# Headers.net
KiCad netlist of a schematic drawn in Altium Designer
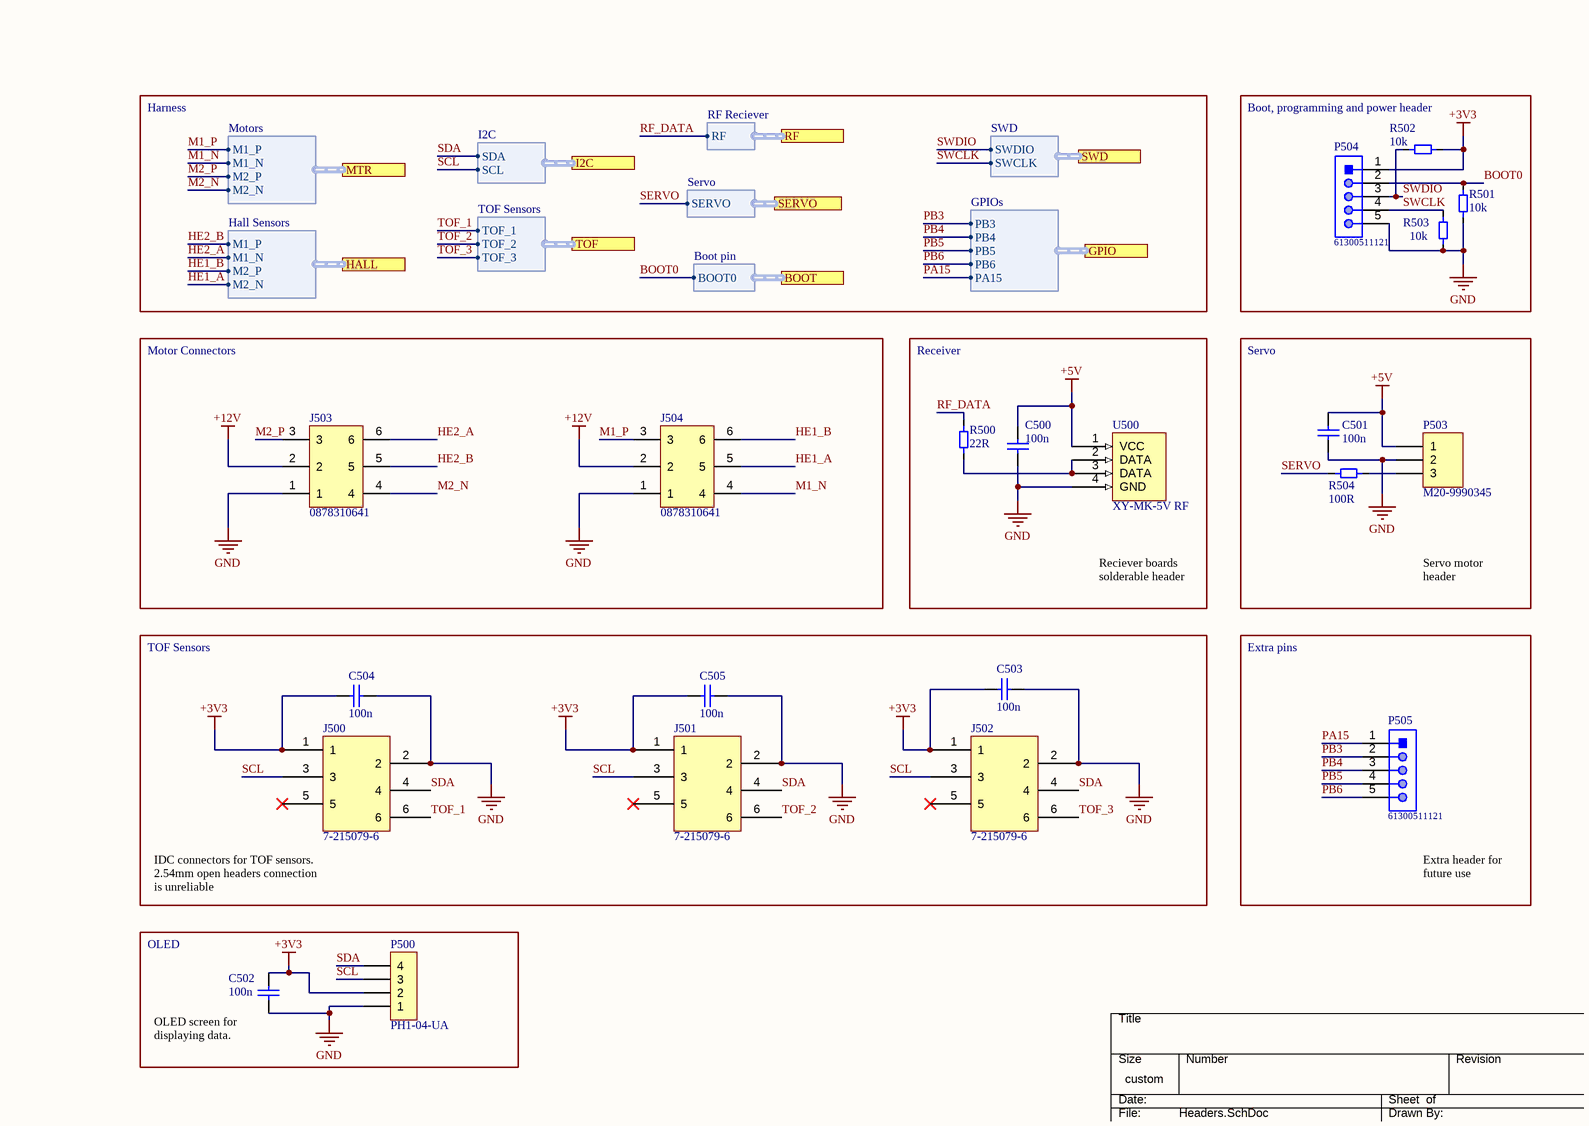
[diagram p0: Headers.SchDoc]

(export (version "E")
  (design (tool "Eeschema 10.0.6"))
  (components
    (comp (ref "C500")
      (value "100n")
      (footprint "MLCC_0603_M")
      (description "MLCC, 0603, 100n, 10%, 50V, X7R")
      (fields (field (name "VOLTAGE") "50V") (field (name "TOLERANCE") "10%"))
      (libsource (lib "Krakul Vault") (part "CAPACITOR_NONPOL_IEC"))
    )
    (comp (ref "C501")
      (value "100n")
      (footprint "MLCC_0603_M")
      (description "MLCC, 0603, 100n, 10%, 50V, X7R")
      (fields (field (name "VOLTAGE") "50V") (field (name "TOLERANCE") "10%"))
      (libsource (lib "Krakul Vault") (part "CAPACITOR_NONPOL_IEC"))
    )
    (comp (ref "C502")
      (value "100n")
      (footprint "MLCC_0603_M")
      (description "MLCC, 0603, 100n, 10%, 50V, X7R")
      (fields (field (name "VOLTAGE") "50V") (field (name "TOLERANCE") "10%"))
      (libsource (lib "Krakul Vault") (part "CAPACITOR_NONPOL_IEC"))
    )
    (comp (ref "C503")
      (value "100n")
      (footprint "MLCC_0603_M")
      (description "MLCC, 0603, 100n, 10%, 50V, X7R")
      (fields (field (name "VOLTAGE") "50V") (field (name "TOLERANCE") "10%"))
      (libsource (lib "Krakul Vault") (part "CAPACITOR_NONPOL_IEC"))
    )
    (comp (ref "C504")
      (value "100n")
      (footprint "MLCC_0603_M")
      (description "MLCC, 0603, 100n, 10%, 50V, X7R")
      (fields (field (name "VOLTAGE") "50V") (field (name "TOLERANCE") "10%"))
      (libsource (lib "Krakul Vault") (part "CAPACITOR_NONPOL_IEC"))
    )
    (comp (ref "C505")
      (value "100n")
      (footprint "MLCC_0603_M")
      (description "MLCC, 0603, 100n, 10%, 50V, X7R")
      (fields (field (name "VOLTAGE") "50V") (field (name "TOLERANCE") "10%"))
      (libsource (lib "Krakul Vault") (part "CAPACITOR_NONPOL_IEC"))
    )
    (comp (ref "J500")
      (value "7-215079-6")
      (footprint "7-215079-6-Footprint-1")
      (description "Conn FFC Connector F 6 POS 1.27mm Solder ST Thru-Hole Automotive Box/Carton")
      (fields (field (name "MANUFACTURER") "TE Connectivity"))
      (libsource (lib "Krakul Vault") (part "7-215079-6"))
    )
    (comp (ref "J501")
      (value "7-215079-6")
      (footprint "7-215079-6-Footprint-1")
      (description "Conn FFC Connector F 6 POS 1.27mm Solder ST Thru-Hole Automotive Box/Carton")
      (fields (field (name "MANUFACTURER") "TE Connectivity"))
      (libsource (lib "Krakul Vault") (part "7-215079-6"))
    )
    (comp (ref "J502")
      (value "7-215079-6")
      (footprint "7-215079-6-Footprint-1")
      (description "Conn FFC Connector F 6 POS 1.27mm Solder ST Thru-Hole Automotive Box/Carton")
      (fields (field (name "MANUFACTURER") "TE Connectivity"))
      (libsource (lib "Krakul Vault") (part "7-215079-6"))
    )
    (comp (ref "J503")
      (value "0878310641")
      (footprint "0878310641")
      (description "Conn Shrouded Header (2 Sides) HDR 6 POS 2mm Solder ST Top Entry Thru-Hole Milli-Grid Tube")
      (fields (field (name "MANUFACTURER") "Molex"))
      (libsource (lib "Krakul Vault") (part "0878310641"))
    )
    (comp (ref "J504")
      (value "0878310641")
      (footprint "0878310641")
      (description "Conn Shrouded Header (2 Sides) HDR 6 POS 2mm Solder ST Top Entry Thru-Hole Milli-Grid Tube")
      (fields (field (name "MANUFACTURER") "Molex"))
      (libsource (lib "Krakul Vault") (part "0878310641"))
    )
    (comp (ref "P500")
      (value "PH1-04-UA")
      (footprint "4Pos Pin Header Vertical")
      (description "4 POS 2.54mm Vertical THT Header")
      (fields (field (name "MANUFACTURER") "Adam Tech"))
      (libsource (lib "Krakul Vault") (part "4POS GENERIC"))
    )
    (comp (ref "P503")
      (value "M20-9990345")
      (footprint "3Pos Pin Header")
      (description "Connector Header Through Hole 3 position 0.100\" (2.54mm)")
      (fields (field (name "MANUFACTURER") "Harwin Inc."))
      (libsource (lib "Krakul Vault") (part "3 pin header"))
    )
    (comp (ref "P504")
      (value "61300511121")
      (footprint "61300511121")
      (description "Conn Unshrouded Header HDR 5 POS 2.54mm Solder ST Top Entry Thru-Hole Bag")
      (fields (field (name "MANUFACTURER") "Wurth"))
      (libsource (lib "") (part "WE-CN-1P-M-R5_1"))
    )
    (comp (ref "P505")
      (value "61300511121")
      (footprint "61300511121")
      (description "Conn Unshrouded Header HDR 5 POS 2.54mm Solder ST Top Entry Thru-Hole Bag")
      (fields (field (name "MANUFACTURER") "Wurth"))
      (libsource (lib "Krakul Vault") (part "WE-CN-1P-M-R5"))
    )
    (comp (ref "R500")
      (value "22R")
      (footprint "Resistor_0603_M")
      (description "Resistor, 0603, 22R, 1%, 1/10W")
      (fields (field (name "TOLERANCE") "1%") (field (name "MANUFACTURER") "Any"))
      (libsource (lib "Krakul Vault") (part "RESISTOR_GENERIC_IEC"))
    )
    (comp (ref "R501")
      (value "10k")
      (footprint "Resistor_0603_M")
      (description "Resistor, 0603, 10k, ≤5%, ≥1/16W")
      (fields (field (name "MANUFACTURER") "Any"))
      (libsource (lib "Krakul Vault") (part "RESISTOR_GENERIC_IEC"))
    )
    (comp (ref "R502")
      (value "10k")
      (footprint "Resistor_0603_M")
      (description "Resistor, 0603, 10k, 1%, 1/10W")
      (fields (field (name "MANUFACTURER") "Any") (field (name "TOLERANCE") "1%"))
      (libsource (lib "Krakul Vault") (part "RESISTOR_GENERIC_IEC"))
    )
    (comp (ref "R503")
      (value "10k")
      (footprint "Resistor_0603_M")
      (description "Resistor, 0603, 10k, 1%, 1/10W")
      (fields (field (name "MANUFACTURER") "Any") (field (name "TOLERANCE") "1%"))
      (libsource (lib "Krakul Vault") (part "RESISTOR_GENERIC_IEC"))
    )
    (comp (ref "R504")
      (value "100R")
      (footprint "Resistor_0603_M")
      (description "Resistor, 0603, 100R, 1%, 1/10W")
      (fields (field (name "POWER") "100mW") (field (name "MANUFACTURER") "Any"))
      (libsource (lib "Krakul Vault") (part "RESISTOR_GENERIC_IEC"))
    )
    (comp (ref "U500")
      (value "XY-MK-5V RF")
      (footprint "2.54mm 4 POS XY-MK-5V RF")
      (description "433MHz reciever module, 5V tolerant")
      (fields (field (name "MANUFACTURER") "Unknown"))
      (libsource (lib "Krakul Vault") (part "XY-MK-5V RF-Symbol-1"))
    )
  )
  (nets
    (net (code "13") (name "+3V3") (class "Default")
      (node (ref "C502") (pin "1") (pinfunction "1_1") (pintype "passive"))
      (node (ref "C503") (pin "1") (pinfunction "1_1") (pintype "passive"))
      (node (ref "C504") (pin "1") (pinfunction "1_1") (pintype "passive"))
      (node (ref "C505") (pin "1") (pinfunction "1_1") (pintype "passive"))
      (node (ref "J500") (pin "1") (pinfunction "1_1") (pintype "passive"))
      (node (ref "J501") (pin "1") (pinfunction "1_1") (pintype "passive"))
      (node (ref "J502") (pin "1") (pinfunction "1_1") (pintype "passive"))
      (node (ref "P500") (pin "2") (pinfunction "2_2") (pintype "passive"))
      (node (ref "P504") (pin "1") (pinfunction "1_1") (pintype "passive"))
      (node (ref "R502") (pin "1") (pinfunction "1_1") (pintype "passive"))
    )
    (net (code "14") (name "+5V") (class "Default")
      (node (ref "C500") (pin "1") (pinfunction "1_1") (pintype "passive"))
      (node (ref "C501") (pin "1") (pinfunction "1_1") (pintype "passive"))
      (node (ref "P503") (pin "1") (pinfunction "1_1") (pintype "passive"))
      (node (ref "U500") (pin "1") (pinfunction "VCC_1") (pintype "input"))
    )
    (net (code "15") (name "+12V") (class "Default")
      (node (ref "J503") (pin "2") (pinfunction "2_2") (pintype "passive"))
      (node (ref "J504") (pin "2") (pinfunction "2_2") (pintype "passive"))
    )
    (net (code "16") (name "/BOOT0") (class "Default")
      (node (ref "P504") (pin "2") (pinfunction "2_2") (pintype "passive"))
      (node (ref "R501") (pin "2") (pinfunction "2_2") (pintype "passive"))
    )
    (net (code "17") (name "/HE1_A") (class "Default")
      (node (ref "J504") (pin "5") (pinfunction "5_5") (pintype "passive"))
    )
    (net (code "18") (name "/HE1_B") (class "Default")
      (node (ref "J504") (pin "6") (pinfunction "6_6") (pintype "passive"))
    )
    (net (code "19") (name "/HE2_A") (class "Default")
      (node (ref "J503") (pin "6") (pinfunction "6_6") (pintype "passive"))
    )
    (net (code "20") (name "/HE2_B") (class "Default")
      (node (ref "J503") (pin "5") (pinfunction "5_5") (pintype "passive"))
    )
    (net (code "21") (name "/M1_N") (class "Default")
      (node (ref "J504") (pin "4") (pinfunction "4_4") (pintype "passive"))
    )
    (net (code "22") (name "/M1_P") (class "Default")
      (node (ref "J504") (pin "3") (pinfunction "3_3") (pintype "passive"))
    )
    (net (code "23") (name "/M2_N") (class "Default")
      (node (ref "J503") (pin "4") (pinfunction "4_4") (pintype "passive"))
    )
    (net (code "24") (name "/M2_P") (class "Default")
      (node (ref "J503") (pin "3") (pinfunction "3_3") (pintype "passive"))
    )
    (net (code "25") (name "/PA15") (class "Default")
      (node (ref "P505") (pin "1") (pinfunction "1_1") (pintype "passive"))
    )
    (net (code "26") (name "/PB3") (class "Default")
      (node (ref "P505") (pin "2") (pinfunction "2_2") (pintype "passive"))
    )
    (net (code "27") (name "/PB4") (class "Default")
      (node (ref "P505") (pin "3") (pinfunction "3_3") (pintype "passive"))
    )
    (net (code "28") (name "/PB5") (class "Default")
      (node (ref "P505") (pin "4") (pinfunction "4_4") (pintype "passive"))
    )
    (net (code "29") (name "/PB6") (class "Default")
      (node (ref "P505") (pin "5") (pinfunction "5_5") (pintype "passive"))
    )
    (net (code "30") (name "/RF_DATA") (class "Default")
      (node (ref "R500") (pin "1") (pinfunction "1_1") (pintype "passive"))
    )
    (net (code "31") (name "/SCL") (class "Default")
      (node (ref "J500") (pin "3") (pinfunction "3_3") (pintype "passive"))
      (node (ref "J501") (pin "3") (pinfunction "3_3") (pintype "passive"))
      (node (ref "J502") (pin "3") (pinfunction "3_3") (pintype "passive"))
      (node (ref "P500") (pin "3") (pinfunction "3_3") (pintype "passive"))
    )
    (net (code "32") (name "/SDA") (class "Default")
      (node (ref "J500") (pin "4") (pinfunction "4_4") (pintype "passive"))
      (node (ref "J501") (pin "4") (pinfunction "4_4") (pintype "passive"))
      (node (ref "J502") (pin "4") (pinfunction "4_4") (pintype "passive"))
      (node (ref "P500") (pin "4") (pinfunction "4_4") (pintype "passive"))
    )
    (net (code "33") (name "/SERVO") (class "Default")
      (node (ref "R504") (pin "2") (pinfunction "2_2") (pintype "passive"))
    )
    (net (code "34") (name "/SWCLK") (class "Default")
      (node (ref "P504") (pin "4") (pinfunction "4_4") (pintype "passive"))
      (node (ref "R503") (pin "2") (pinfunction "2_2") (pintype "passive"))
    )
    (net (code "35") (name "/SWDIO") (class "Default")
      (node (ref "P504") (pin "3") (pinfunction "3_3") (pintype "passive"))
      (node (ref "R502") (pin "2") (pinfunction "2_2") (pintype "passive"))
    )
    (net (code "36") (name "/TOF_1") (class "Default")
      (node (ref "J500") (pin "6") (pinfunction "6_6") (pintype "passive"))
    )
    (net (code "37") (name "/TOF_2") (class "Default")
      (node (ref "J501") (pin "6") (pinfunction "6_6") (pintype "passive"))
    )
    (net (code "38") (name "/TOF_3") (class "Default")
      (node (ref "J502") (pin "6") (pinfunction "6_6") (pintype "passive"))
    )
    (net (code "48") (name "GND") (class "Default")
      (node (ref "C500") (pin "2") (pinfunction "2_2") (pintype "passive"))
      (node (ref "C501") (pin "2") (pinfunction "2_2") (pintype "passive"))
      (node (ref "C502") (pin "2") (pinfunction "2_2") (pintype "passive"))
      (node (ref "C503") (pin "2") (pinfunction "2_2") (pintype "passive"))
      (node (ref "C504") (pin "2") (pinfunction "2_2") (pintype "passive"))
      (node (ref "C505") (pin "2") (pinfunction "2_2") (pintype "passive"))
      (node (ref "J500") (pin "2") (pinfunction "2_2") (pintype "passive"))
      (node (ref "J501") (pin "2") (pinfunction "2_2") (pintype "passive"))
      (node (ref "J502") (pin "2") (pinfunction "2_2") (pintype "passive"))
      (node (ref "J503") (pin "1") (pinfunction "1_1") (pintype "passive"))
      (node (ref "J504") (pin "1") (pinfunction "1_1") (pintype "passive"))
      (node (ref "P500") (pin "1") (pinfunction "1_1") (pintype "passive"))
      (node (ref "P503") (pin "2") (pinfunction "2_2") (pintype "passive"))
      (node (ref "P504") (pin "5") (pinfunction "5_5") (pintype "passive"))
      (node (ref "R501") (pin "1") (pinfunction "1_1") (pintype "passive"))
      (node (ref "R503") (pin "1") (pinfunction "1_1") (pintype "passive"))
      (node (ref "U500") (pin "4") (pinfunction "GND_4") (pintype "input"))
    )
    (net (code "49") (name "Net-(P503-Pad3)") (class "Default")
      (node (ref "P503") (pin "3") (pinfunction "3_3") (pintype "passive"))
      (node (ref "R504") (pin "1") (pinfunction "1_1") (pintype "passive"))
    )
    (net (code "50") (name "Net-(R500-Pad2)") (class "Default")
      (node (ref "R500") (pin "2") (pinfunction "2_2") (pintype "passive"))
      (node (ref "U500") (pin "2") (pinfunction "DATA_2") (pintype "input"))
      (node (ref "U500") (pin "3") (pinfunction "DATA_3") (pintype "input"))
    )
    (net (code "51") (name "unconnected-(J500-Pad5)") (class "Default")
      (node (ref "J500") (pin "5") (pinfunction "5_5") (pintype "passive+no_connect"))
    )
    (net (code "52") (name "unconnected-(J501-Pad5)") (class "Default")
      (node (ref "J501") (pin "5") (pinfunction "5_5") (pintype "passive+no_connect"))
    )
    (net (code "53") (name "unconnected-(J502-Pad5)") (class "Default")
      (node (ref "J502") (pin "5") (pinfunction "5_5") (pintype "passive+no_connect"))
    )
  )
)
